# e-wall.net
KiCad netlist of a schematic drawn in EAGLE
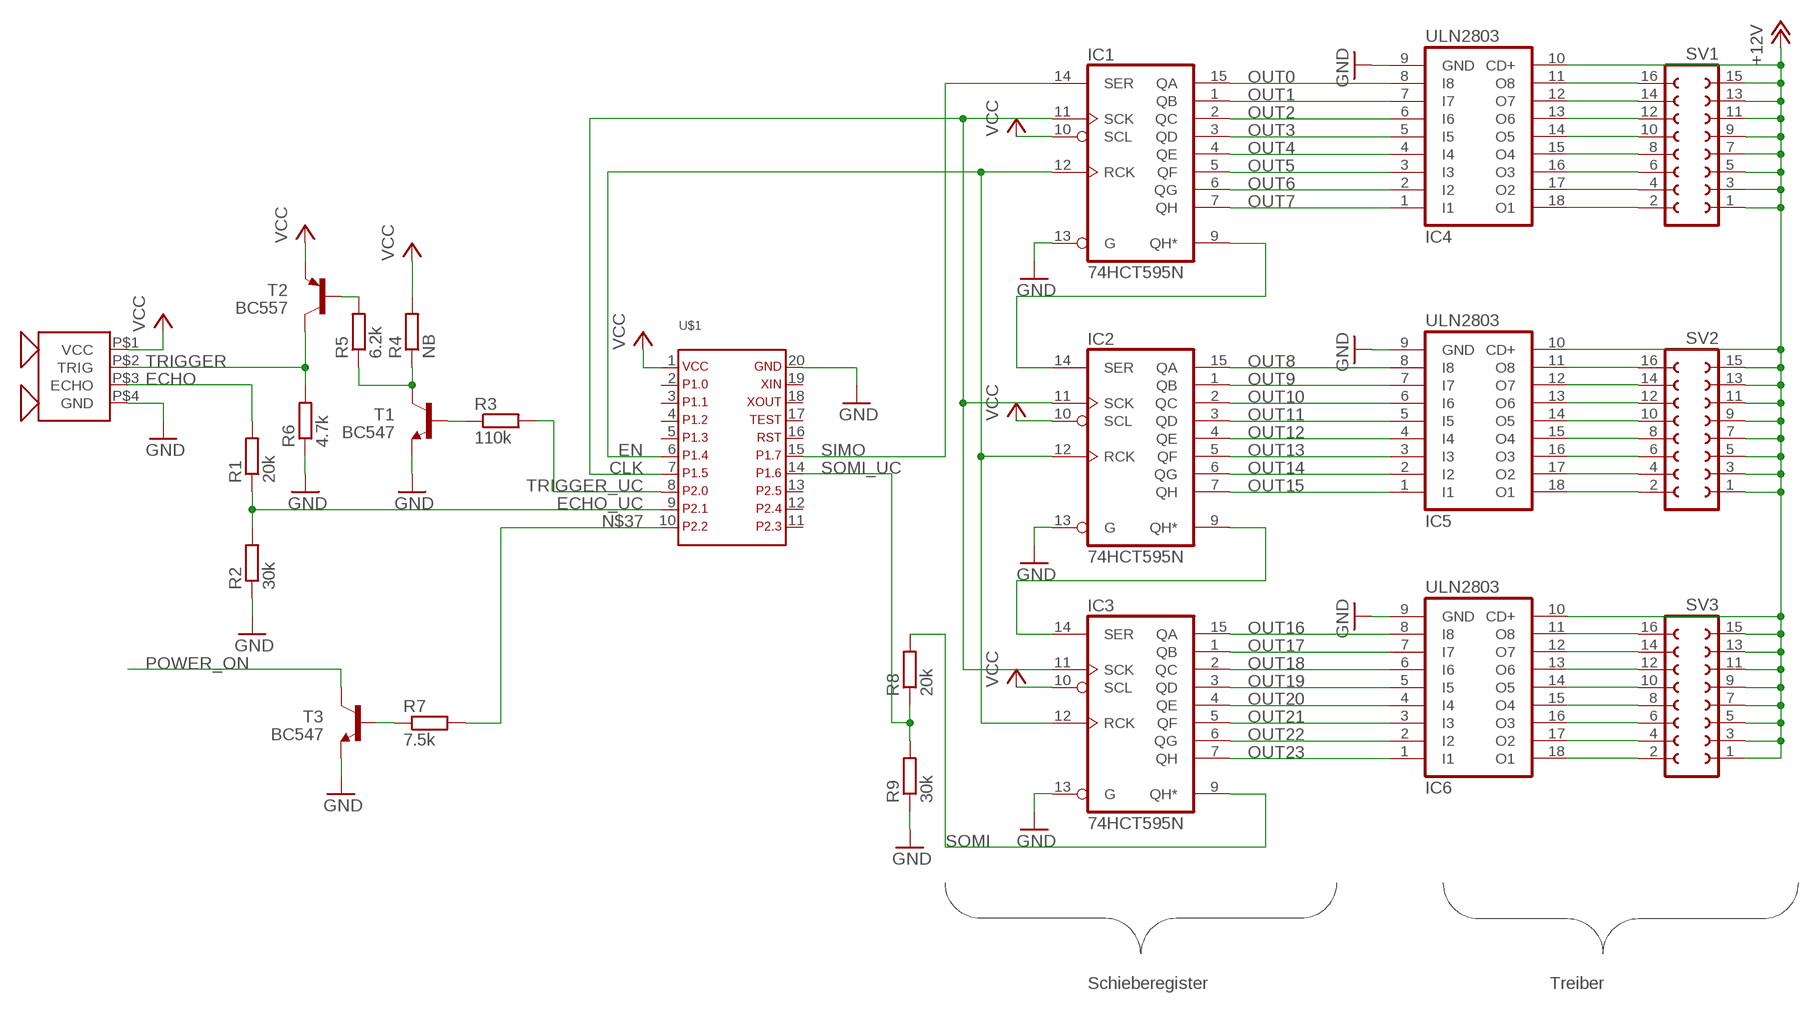
[diagram p0: schematic, sheet 1]

(export (version "E")
  (design (tool "Eeschema 10.0.6"))
  (components
    (comp (ref "IC1")
      (value "74HCT595N")
      (footprint "eagle-import:DIL16")
      (libsource (lib "eagle-import") (part "74595NHCT"))
    )
    (comp (ref "IC2")
      (value "74HCT595N")
      (footprint "eagle-import:DIL16")
      (libsource (lib "eagle-import") (part "74595NHCT"))
    )
    (comp (ref "IC3")
      (value "74HCT595N")
      (footprint "eagle-import:DIL16")
      (libsource (lib "eagle-import") (part "74595NHCT"))
    )
    (comp (ref "IC4")
      (value "ULN2803")
      (footprint "eagle-import:DIL18")
      (libsource (lib "eagle-import") (part "ULN2803A"))
    )
    (comp (ref "IC5")
      (value "ULN2803")
      (footprint "eagle-import:DIL18")
      (libsource (lib "eagle-import") (part "ULN2803A"))
    )
    (comp (ref "IC6")
      (value "ULN2803")
      (footprint "eagle-import:DIL18")
      (libsource (lib "eagle-import") (part "ULN2803A"))
    )
    (comp (ref "R1")
      (value "20k")
      (footprint "eagle-import:0207_7")
      (libsource (lib "eagle-import") (part "R-EU_0207/7"))
    )
    (comp (ref "R2")
      (value "30k")
      (footprint "eagle-import:0207_7")
      (libsource (lib "eagle-import") (part "R-EU_0207/7"))
    )
    (comp (ref "R3")
      (value "110k")
      (footprint "eagle-import:0207_7")
      (libsource (lib "eagle-import") (part "R-EU_0207/7"))
    )
    (comp (ref "R4")
      (value "NB")
      (footprint "eagle-import:0207_2V")
      (libsource (lib "eagle-import") (part "R-EU_0207/2V"))
    )
    (comp (ref "R5")
      (value "6.2k")
      (footprint "eagle-import:0207_2V")
      (libsource (lib "eagle-import") (part "R-EU_0207/2V"))
    )
    (comp (ref "R6")
      (value "4.7k")
      (footprint "eagle-import:0207_7")
      (libsource (lib "eagle-import") (part "R-EU_0207/7"))
    )
    (comp (ref "R7")
      (value "7.5k")
      (footprint "eagle-import:0207_7")
      (libsource (lib "eagle-import") (part "R-EU_0207/7"))
    )
    (comp (ref "R8")
      (value "20k")
      (footprint "eagle-import:0207_7")
      (libsource (lib "eagle-import") (part "R-EU_0207/7"))
    )
    (comp (ref "R9")
      (value "30k")
      (footprint "eagle-import:0207_7")
      (libsource (lib "eagle-import") (part "R-EU_0207/7"))
    )
    (comp (ref "SV1")
      (value "FE08-2")
      (footprint "eagle-import:FE08-2")
      (libsource (lib "eagle-import") (part "FE08-2"))
    )
    (comp (ref "SV2")
      (value "FE08-2")
      (footprint "eagle-import:FE08-2")
      (libsource (lib "eagle-import") (part "FE08-2"))
    )
    (comp (ref "SV3")
      (value "FE08-2")
      (footprint "eagle-import:FE08-2")
      (libsource (lib "eagle-import") (part "FE08-2"))
    )
    (comp (ref "T1")
      (value "BC547")
      (footprint "eagle-import:TO92-EBC")
      (libsource (lib "eagle-import") (part "-NPN-TO92-EBC"))
    )
    (comp (ref "T2")
      (value "BC557")
      (footprint "eagle-import:TO92-BEC")
      (libsource (lib "eagle-import") (part "-PNP-TO92-BEC"))
    )
    (comp (ref "T3")
      (value "BC547")
      (footprint "eagle-import:TO92-EBC")
      (libsource (lib "eagle-import") (part "-NPN-TO92-EBC"))
    )
    (comp (ref "U$1")
      (value "MSP430LAUNCHPAD_BASIC")
      (footprint "eagle-import:MSP430LAUNCHPAD_BASIC")
      (libsource (lib "eagle-import") (part "MSP430LAUNCHPAD_BASIC"))
    )
    (comp (ref "U$2")
      (value "HC-SR04")
      (footprint "eagle-import:HC-SR04")
      (libsource (lib "eagle-import") (part "HC-SR04"))
    )
  )
  (nets
    (net (code "1") (name "+12V") (class "Default")
      (node (ref "IC4") (pin "10") (pinfunction "CD+_10") (pintype "passive"))
      (node (ref "IC5") (pin "10") (pinfunction "CD+_10") (pintype "passive"))
      (node (ref "IC6") (pin "10") (pinfunction "CD+_10") (pintype "passive"))
      (node (ref "SV1") (pin "1") (pinfunction "1_1") (pintype "passive"))
      (node (ref "SV1") (pin "11") (pinfunction "11_11") (pintype "passive"))
      (node (ref "SV1") (pin "13") (pinfunction "13_13") (pintype "passive"))
      (node (ref "SV1") (pin "15") (pinfunction "15_15") (pintype "passive"))
      (node (ref "SV1") (pin "3") (pinfunction "3_3") (pintype "passive"))
      (node (ref "SV1") (pin "5") (pinfunction "5_5") (pintype "passive"))
      (node (ref "SV1") (pin "7") (pinfunction "7_7") (pintype "passive"))
      (node (ref "SV1") (pin "9") (pinfunction "9_9") (pintype "passive"))
      (node (ref "SV2") (pin "1") (pinfunction "1_1") (pintype "passive"))
      (node (ref "SV2") (pin "11") (pinfunction "11_11") (pintype "passive"))
      (node (ref "SV2") (pin "13") (pinfunction "13_13") (pintype "passive"))
      (node (ref "SV2") (pin "15") (pinfunction "15_15") (pintype "passive"))
      (node (ref "SV2") (pin "3") (pinfunction "3_3") (pintype "passive"))
      (node (ref "SV2") (pin "5") (pinfunction "5_5") (pintype "passive"))
      (node (ref "SV2") (pin "7") (pinfunction "7_7") (pintype "passive"))
      (node (ref "SV2") (pin "9") (pinfunction "9_9") (pintype "passive"))
      (node (ref "SV3") (pin "1") (pinfunction "1_1") (pintype "passive"))
      (node (ref "SV3") (pin "11") (pinfunction "11_11") (pintype "passive"))
      (node (ref "SV3") (pin "13") (pinfunction "13_13") (pintype "passive"))
      (node (ref "SV3") (pin "15") (pinfunction "15_15") (pintype "passive"))
      (node (ref "SV3") (pin "3") (pinfunction "3_3") (pintype "passive"))
      (node (ref "SV3") (pin "5") (pinfunction "5_5") (pintype "passive"))
      (node (ref "SV3") (pin "7") (pinfunction "7_7") (pintype "passive"))
      (node (ref "SV3") (pin "9") (pinfunction "9_9") (pintype "passive"))
    )
    (net (code "2") (name "/CLK") (class "Default")
      (node (ref "IC1") (pin "11") (pinfunction "SCK_11") (pintype "input"))
      (node (ref "IC2") (pin "11") (pinfunction "SCK_11") (pintype "input"))
      (node (ref "IC3") (pin "11") (pinfunction "SCK_11") (pintype "input"))
      (node (ref "U$1") (pin "7") (pinfunction "7_7") (pintype "bidirectional"))
    )
    (net (code "3") (name "/ECHO") (class "Default")
      (node (ref "R1") (pin "2") (pinfunction "2_2") (pintype "passive"))
      (node (ref "U$2") (pin "P$3") (pinfunction "ECHO_P$3") (pintype "bidirectional"))
    )
    (net (code "4") (name "/ECHO_UC") (class "Default")
      (node (ref "R1") (pin "1") (pinfunction "1_1") (pintype "passive"))
      (node (ref "R2") (pin "2") (pinfunction "2_2") (pintype "passive"))
      (node (ref "U$1") (pin "9") (pinfunction "9_9") (pintype "bidirectional"))
    )
    (net (code "5") (name "/EN") (class "Default")
      (node (ref "IC1") (pin "12") (pinfunction "RCK_12") (pintype "input"))
      (node (ref "IC2") (pin "12") (pinfunction "RCK_12") (pintype "input"))
      (node (ref "IC3") (pin "12") (pinfunction "RCK_12") (pintype "input"))
      (node (ref "U$1") (pin "6") (pinfunction "6_6") (pintype "bidirectional"))
    )
    (net (code "6") (name "/N$37") (class "Default")
      (node (ref "R7") (pin "2") (pinfunction "2_2") (pintype "passive"))
      (node (ref "U$1") (pin "10") (pinfunction "10_10") (pintype "bidirectional"))
    )
    (net (code "7") (name "/OUT0") (class "Default")
      (node (ref "IC1") (pin "15") (pinfunction "QA_15") (pintype "tri_state"))
      (node (ref "IC4") (pin "8") (pinfunction "I8_8") (pintype "input"))
    )
    (net (code "8") (name "/OUT1") (class "Default")
      (node (ref "IC1") (pin "1") (pinfunction "QB_1") (pintype "tri_state"))
      (node (ref "IC4") (pin "7") (pinfunction "I7_7") (pintype "input"))
    )
    (net (code "9") (name "/OUT2") (class "Default")
      (node (ref "IC1") (pin "2") (pinfunction "QC_2") (pintype "tri_state"))
      (node (ref "IC4") (pin "6") (pinfunction "I6_6") (pintype "input"))
    )
    (net (code "10") (name "/OUT3") (class "Default")
      (node (ref "IC1") (pin "3") (pinfunction "QD_3") (pintype "tri_state"))
      (node (ref "IC4") (pin "5") (pinfunction "I5_5") (pintype "input"))
    )
    (net (code "11") (name "/OUT4") (class "Default")
      (node (ref "IC1") (pin "4") (pinfunction "QE_4") (pintype "tri_state"))
      (node (ref "IC4") (pin "4") (pinfunction "I4_4") (pintype "input"))
    )
    (net (code "12") (name "/OUT5") (class "Default")
      (node (ref "IC1") (pin "5") (pinfunction "QF_5") (pintype "tri_state"))
      (node (ref "IC4") (pin "3") (pinfunction "I3_3") (pintype "input"))
    )
    (net (code "13") (name "/OUT6") (class "Default")
      (node (ref "IC1") (pin "6") (pinfunction "QG_6") (pintype "tri_state"))
      (node (ref "IC4") (pin "2") (pinfunction "I2_2") (pintype "input"))
    )
    (net (code "14") (name "/OUT7") (class "Default")
      (node (ref "IC1") (pin "7") (pinfunction "QH_7") (pintype "tri_state"))
      (node (ref "IC4") (pin "1") (pinfunction "I1_1") (pintype "input"))
    )
    (net (code "15") (name "/OUT8") (class "Default")
      (node (ref "IC2") (pin "15") (pinfunction "QA_15") (pintype "tri_state"))
      (node (ref "IC5") (pin "8") (pinfunction "I8_8") (pintype "input"))
    )
    (net (code "16") (name "/OUT9") (class "Default")
      (node (ref "IC2") (pin "1") (pinfunction "QB_1") (pintype "tri_state"))
      (node (ref "IC5") (pin "7") (pinfunction "I7_7") (pintype "input"))
    )
    (net (code "17") (name "/OUT10") (class "Default")
      (node (ref "IC2") (pin "2") (pinfunction "QC_2") (pintype "tri_state"))
      (node (ref "IC5") (pin "6") (pinfunction "I6_6") (pintype "input"))
    )
    (net (code "18") (name "/OUT11") (class "Default")
      (node (ref "IC2") (pin "3") (pinfunction "QD_3") (pintype "tri_state"))
      (node (ref "IC5") (pin "5") (pinfunction "I5_5") (pintype "input"))
    )
    (net (code "19") (name "/OUT12") (class "Default")
      (node (ref "IC2") (pin "4") (pinfunction "QE_4") (pintype "tri_state"))
      (node (ref "IC5") (pin "4") (pinfunction "I4_4") (pintype "input"))
    )
    (net (code "20") (name "/OUT13") (class "Default")
      (node (ref "IC2") (pin "5") (pinfunction "QF_5") (pintype "tri_state"))
      (node (ref "IC5") (pin "3") (pinfunction "I3_3") (pintype "input"))
    )
    (net (code "21") (name "/OUT14") (class "Default")
      (node (ref "IC2") (pin "6") (pinfunction "QG_6") (pintype "tri_state"))
      (node (ref "IC5") (pin "2") (pinfunction "I2_2") (pintype "input"))
    )
    (net (code "22") (name "/OUT15") (class "Default")
      (node (ref "IC2") (pin "7") (pinfunction "QH_7") (pintype "tri_state"))
      (node (ref "IC5") (pin "1") (pinfunction "I1_1") (pintype "input"))
    )
    (net (code "23") (name "/OUT16") (class "Default")
      (node (ref "IC3") (pin "15") (pinfunction "QA_15") (pintype "tri_state"))
      (node (ref "IC6") (pin "8") (pinfunction "I8_8") (pintype "input"))
    )
    (net (code "24") (name "/OUT17") (class "Default")
      (node (ref "IC3") (pin "1") (pinfunction "QB_1") (pintype "tri_state"))
      (node (ref "IC6") (pin "7") (pinfunction "I7_7") (pintype "input"))
    )
    (net (code "25") (name "/OUT18") (class "Default")
      (node (ref "IC3") (pin "2") (pinfunction "QC_2") (pintype "tri_state"))
      (node (ref "IC6") (pin "6") (pinfunction "I6_6") (pintype "input"))
    )
    (net (code "26") (name "/OUT19") (class "Default")
      (node (ref "IC3") (pin "3") (pinfunction "QD_3") (pintype "tri_state"))
      (node (ref "IC6") (pin "5") (pinfunction "I5_5") (pintype "input"))
    )
    (net (code "27") (name "/OUT20") (class "Default")
      (node (ref "IC3") (pin "4") (pinfunction "QE_4") (pintype "tri_state"))
      (node (ref "IC6") (pin "4") (pinfunction "I4_4") (pintype "input"))
    )
    (net (code "28") (name "/OUT21") (class "Default")
      (node (ref "IC3") (pin "5") (pinfunction "QF_5") (pintype "tri_state"))
      (node (ref "IC6") (pin "3") (pinfunction "I3_3") (pintype "input"))
    )
    (net (code "29") (name "/OUT22") (class "Default")
      (node (ref "IC3") (pin "6") (pinfunction "QG_6") (pintype "tri_state"))
      (node (ref "IC6") (pin "2") (pinfunction "I2_2") (pintype "input"))
    )
    (net (code "30") (name "/OUT23") (class "Default")
      (node (ref "IC3") (pin "7") (pinfunction "QH_7") (pintype "tri_state"))
      (node (ref "IC6") (pin "1") (pinfunction "I1_1") (pintype "input"))
    )
    (net (code "31") (name "/POWER_ON") (class "Default")
      (node (ref "T3") (pin "C") (pinfunction "C_C") (pintype "passive"))
    )
    (net (code "32") (name "/SIMO") (class "Default")
      (node (ref "IC1") (pin "14") (pinfunction "SER_14") (pintype "input"))
      (node (ref "U$1") (pin "15") (pinfunction "15_15") (pintype "bidirectional"))
    )
    (net (code "33") (name "/SOMI") (class "Default")
      (node (ref "IC3") (pin "9") (pinfunction "QH*_9") (pintype "tri_state"))
      (node (ref "R8") (pin "2") (pinfunction "2_2") (pintype "passive"))
    )
    (net (code "34") (name "/SOMI_UC") (class "Default")
      (node (ref "R8") (pin "1") (pinfunction "1_1") (pintype "passive"))
      (node (ref "R9") (pin "2") (pinfunction "2_2") (pintype "passive"))
      (node (ref "U$1") (pin "14") (pinfunction "14_14") (pintype "bidirectional"))
    )
    (net (code "35") (name "/TRIGGER") (class "Default")
      (node (ref "R6") (pin "2") (pinfunction "2_2") (pintype "passive"))
      (node (ref "T2") (pin "C") (pinfunction "C_C") (pintype "passive"))
      (node (ref "U$2") (pin "P$2") (pinfunction "TRIG_P$2") (pintype "bidirectional"))
    )
    (net (code "36") (name "/TRIGGER_UC") (class "Default")
      (node (ref "R3") (pin "2") (pinfunction "2_2") (pintype "passive"))
      (node (ref "U$1") (pin "8") (pinfunction "8_8") (pintype "bidirectional"))
    )
    (net (code "37") (name "GND") (class "Default")
      (node (ref "IC1") (pin "13") (pinfunction "G_13") (pintype "input"))
      (node (ref "IC2") (pin "13") (pinfunction "G_13") (pintype "input"))
      (node (ref "IC3") (pin "13") (pinfunction "G_13") (pintype "input"))
      (node (ref "IC4") (pin "9") (pinfunction "GND_9") (pintype "power_in"))
      (node (ref "IC5") (pin "9") (pinfunction "GND_9") (pintype "power_in"))
      (node (ref "IC6") (pin "9") (pinfunction "GND_9") (pintype "power_in"))
      (node (ref "R2") (pin "1") (pinfunction "1_1") (pintype "passive"))
      (node (ref "R6") (pin "1") (pinfunction "1_1") (pintype "passive"))
      (node (ref "R9") (pin "1") (pinfunction "1_1") (pintype "passive"))
      (node (ref "T1") (pin "E") (pinfunction "E_E") (pintype "passive"))
      (node (ref "T3") (pin "E") (pinfunction "E_E") (pintype "passive"))
      (node (ref "U$1") (pin "20") (pinfunction "20_20") (pintype "bidirectional"))
      (node (ref "U$2") (pin "P$4") (pinfunction "GND_P$4") (pintype "bidirectional"))
    )
    (net (code "38") (name "Net-(IC1A-QH*)") (class "Default")
      (node (ref "IC1") (pin "9") (pinfunction "QH*_9") (pintype "tri_state"))
      (node (ref "IC2") (pin "14") (pinfunction "SER_14") (pintype "input"))
    )
    (net (code "39") (name "Net-(IC2A-QH*)") (class "Default")
      (node (ref "IC2") (pin "9") (pinfunction "QH*_9") (pintype "tri_state"))
      (node (ref "IC3") (pin "14") (pinfunction "SER_14") (pintype "input"))
    )
    (net (code "40") (name "Net-(IC4-O1)") (class "Default")
      (node (ref "IC4") (pin "18") (pinfunction "O1_18") (pintype "open_collector"))
      (node (ref "SV1") (pin "2") (pinfunction "2_2") (pintype "passive"))
    )
    (net (code "41") (name "Net-(IC4-O2)") (class "Default")
      (node (ref "IC4") (pin "17") (pinfunction "O2_17") (pintype "open_collector"))
      (node (ref "SV1") (pin "4") (pinfunction "4_4") (pintype "passive"))
    )
    (net (code "42") (name "Net-(IC4-O3)") (class "Default")
      (node (ref "IC4") (pin "16") (pinfunction "O3_16") (pintype "open_collector"))
      (node (ref "SV1") (pin "6") (pinfunction "6_6") (pintype "passive"))
    )
    (net (code "43") (name "Net-(IC4-O4)") (class "Default")
      (node (ref "IC4") (pin "15") (pinfunction "O4_15") (pintype "open_collector"))
      (node (ref "SV1") (pin "8") (pinfunction "8_8") (pintype "passive"))
    )
    (net (code "44") (name "Net-(IC4-O5)") (class "Default")
      (node (ref "IC4") (pin "14") (pinfunction "O5_14") (pintype "open_collector"))
      (node (ref "SV1") (pin "10") (pinfunction "10_10") (pintype "passive"))
    )
    (net (code "45") (name "Net-(IC4-O6)") (class "Default")
      (node (ref "IC4") (pin "13") (pinfunction "O6_13") (pintype "open_collector"))
      (node (ref "SV1") (pin "12") (pinfunction "12_12") (pintype "passive"))
    )
    (net (code "46") (name "Net-(IC4-O7)") (class "Default")
      (node (ref "IC4") (pin "12") (pinfunction "O7_12") (pintype "open_collector"))
      (node (ref "SV1") (pin "14") (pinfunction "14_14") (pintype "passive"))
    )
    (net (code "47") (name "Net-(IC4-O8)") (class "Default")
      (node (ref "IC4") (pin "11") (pinfunction "O8_11") (pintype "open_collector"))
      (node (ref "SV1") (pin "16") (pinfunction "16_16") (pintype "passive"))
    )
    (net (code "48") (name "Net-(IC5-O1)") (class "Default")
      (node (ref "IC5") (pin "18") (pinfunction "O1_18") (pintype "open_collector"))
      (node (ref "SV2") (pin "2") (pinfunction "2_2") (pintype "passive"))
    )
    (net (code "49") (name "Net-(IC5-O2)") (class "Default")
      (node (ref "IC5") (pin "17") (pinfunction "O2_17") (pintype "open_collector"))
      (node (ref "SV2") (pin "4") (pinfunction "4_4") (pintype "passive"))
    )
    (net (code "50") (name "Net-(IC5-O3)") (class "Default")
      (node (ref "IC5") (pin "16") (pinfunction "O3_16") (pintype "open_collector"))
      (node (ref "SV2") (pin "6") (pinfunction "6_6") (pintype "passive"))
    )
    (net (code "51") (name "Net-(IC5-O4)") (class "Default")
      (node (ref "IC5") (pin "15") (pinfunction "O4_15") (pintype "open_collector"))
      (node (ref "SV2") (pin "8") (pinfunction "8_8") (pintype "passive"))
    )
    (net (code "52") (name "Net-(IC5-O5)") (class "Default")
      (node (ref "IC5") (pin "14") (pinfunction "O5_14") (pintype "open_collector"))
      (node (ref "SV2") (pin "10") (pinfunction "10_10") (pintype "passive"))
    )
    (net (code "53") (name "Net-(IC5-O6)") (class "Default")
      (node (ref "IC5") (pin "13") (pinfunction "O6_13") (pintype "open_collector"))
      (node (ref "SV2") (pin "12") (pinfunction "12_12") (pintype "passive"))
    )
    (net (code "54") (name "Net-(IC5-O7)") (class "Default")
      (node (ref "IC5") (pin "12") (pinfunction "O7_12") (pintype "open_collector"))
      (node (ref "SV2") (pin "14") (pinfunction "14_14") (pintype "passive"))
    )
    (net (code "55") (name "Net-(IC5-O8)") (class "Default")
      (node (ref "IC5") (pin "11") (pinfunction "O8_11") (pintype "open_collector"))
      (node (ref "SV2") (pin "16") (pinfunction "16_16") (pintype "passive"))
    )
    (net (code "56") (name "Net-(IC6-O1)") (class "Default")
      (node (ref "IC6") (pin "18") (pinfunction "O1_18") (pintype "open_collector"))
      (node (ref "SV3") (pin "2") (pinfunction "2_2") (pintype "passive"))
    )
    (net (code "57") (name "Net-(IC6-O2)") (class "Default")
      (node (ref "IC6") (pin "17") (pinfunction "O2_17") (pintype "open_collector"))
      (node (ref "SV3") (pin "4") (pinfunction "4_4") (pintype "passive"))
    )
    (net (code "58") (name "Net-(IC6-O3)") (class "Default")
      (node (ref "IC6") (pin "16") (pinfunction "O3_16") (pintype "open_collector"))
      (node (ref "SV3") (pin "6") (pinfunction "6_6") (pintype "passive"))
    )
    (net (code "59") (name "Net-(IC6-O4)") (class "Default")
      (node (ref "IC6") (pin "15") (pinfunction "O4_15") (pintype "open_collector"))
      (node (ref "SV3") (pin "8") (pinfunction "8_8") (pintype "passive"))
    )
    (net (code "60") (name "Net-(IC6-O5)") (class "Default")
      (node (ref "IC6") (pin "14") (pinfunction "O5_14") (pintype "open_collector"))
      (node (ref "SV3") (pin "10") (pinfunction "10_10") (pintype "passive"))
    )
    (net (code "61") (name "Net-(IC6-O6)") (class "Default")
      (node (ref "IC6") (pin "13") (pinfunction "O6_13") (pintype "open_collector"))
      (node (ref "SV3") (pin "12") (pinfunction "12_12") (pintype "passive"))
    )
    (net (code "62") (name "Net-(IC6-O7)") (class "Default")
      (node (ref "IC6") (pin "12") (pinfunction "O7_12") (pintype "open_collector"))
      (node (ref "SV3") (pin "14") (pinfunction "14_14") (pintype "passive"))
    )
    (net (code "63") (name "Net-(IC6-O8)") (class "Default")
      (node (ref "IC6") (pin "11") (pinfunction "O8_11") (pintype "open_collector"))
      (node (ref "SV3") (pin "16") (pinfunction "16_16") (pintype "passive"))
    )
    (net (code "64") (name "Net-(R3-Pad1)") (class "Default")
      (node (ref "R3") (pin "1") (pinfunction "1_1") (pintype "passive"))
      (node (ref "T1") (pin "B") (pinfunction "B_B") (pintype "passive"))
    )
    (net (code "65") (name "Net-(R4-Pad1)") (class "Default")
      (node (ref "R4") (pin "1") (pinfunction "1_1") (pintype "passive"))
      (node (ref "R5") (pin "1") (pinfunction "1_1") (pintype "passive"))
      (node (ref "T1") (pin "C") (pinfunction "C_C") (pintype "passive"))
    )
    (net (code "66") (name "Net-(R5-Pad2)") (class "Default")
      (node (ref "R5") (pin "2") (pinfunction "2_2") (pintype "passive"))
      (node (ref "T2") (pin "B") (pinfunction "B_B") (pintype "passive"))
    )
    (net (code "67") (name "Net-(R7-Pad1)") (class "Default")
      (node (ref "R7") (pin "1") (pinfunction "1_1") (pintype "passive"))
      (node (ref "T3") (pin "B") (pinfunction "B_B") (pintype "passive"))
    )
    (net (code "68") (name "VCC") (class "Default")
      (node (ref "IC1") (pin "10") (pinfunction "SCL_10") (pintype "input"))
      (node (ref "IC2") (pin "10") (pinfunction "SCL_10") (pintype "input"))
      (node (ref "IC3") (pin "10") (pinfunction "SCL_10") (pintype "input"))
      (node (ref "R4") (pin "2") (pinfunction "2_2") (pintype "passive"))
      (node (ref "T2") (pin "E") (pinfunction "E_E") (pintype "passive"))
      (node (ref "U$1") (pin "1") (pinfunction "1_1") (pintype "bidirectional"))
      (node (ref "U$2") (pin "P$1") (pinfunction "VCC_P$1") (pintype "bidirectional"))
    )
    (net (code "69") (name "unconnected-(U$1-Pad2)") (class "Default")
      (node (ref "U$1") (pin "2") (pinfunction "2_2") (pintype "bidirectional"))
    )
    (net (code "70") (name "unconnected-(U$1-Pad3)") (class "Default")
      (node (ref "U$1") (pin "3") (pinfunction "3_3") (pintype "bidirectional"))
    )
    (net (code "71") (name "unconnected-(U$1-Pad4)") (class "Default")
      (node (ref "U$1") (pin "4") (pinfunction "4_4") (pintype "bidirectional"))
    )
    (net (code "72") (name "unconnected-(U$1-Pad5)") (class "Default")
      (node (ref "U$1") (pin "5") (pinfunction "5_5") (pintype "bidirectional"))
    )
    (net (code "73") (name "unconnected-(U$1-Pad11)") (class "Default")
      (node (ref "U$1") (pin "11") (pinfunction "11_11") (pintype "bidirectional"))
    )
    (net (code "74") (name "unconnected-(U$1-Pad12)") (class "Default")
      (node (ref "U$1") (pin "12") (pinfunction "12_12") (pintype "bidirectional"))
    )
    (net (code "75") (name "unconnected-(U$1-Pad13)") (class "Default")
      (node (ref "U$1") (pin "13") (pinfunction "13_13") (pintype "bidirectional"))
    )
    (net (code "76") (name "unconnected-(U$1-Pad16)") (class "Default")
      (node (ref "U$1") (pin "16") (pinfunction "16_16") (pintype "bidirectional"))
    )
    (net (code "77") (name "unconnected-(U$1-Pad17)") (class "Default")
      (node (ref "U$1") (pin "17") (pinfunction "17_17") (pintype "bidirectional"))
    )
    (net (code "78") (name "unconnected-(U$1-Pad18)") (class "Default")
      (node (ref "U$1") (pin "18") (pinfunction "18_18") (pintype "bidirectional"))
    )
    (net (code "79") (name "unconnected-(U$1-Pad19)") (class "Default")
      (node (ref "U$1") (pin "19") (pinfunction "19_19") (pintype "bidirectional"))
    )
  )
)
